# RFM23BPW_Breakout_Board.net
KiCad netlist of a schematic drawn in EAGLE
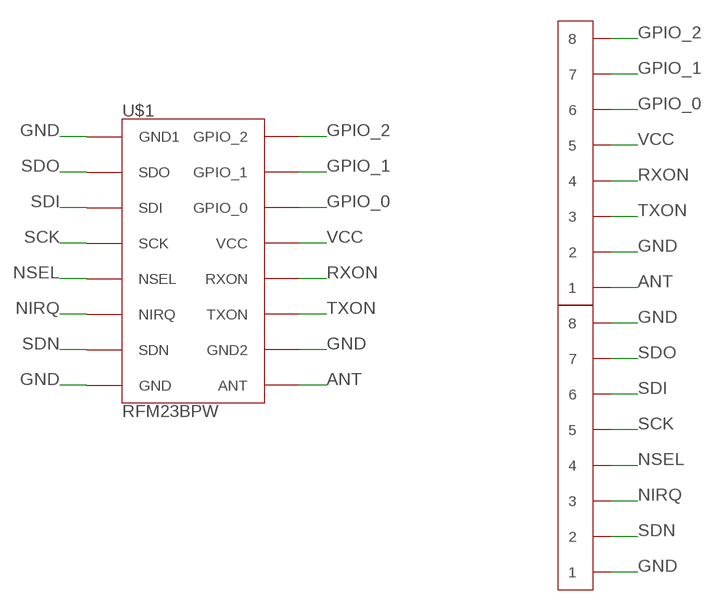
[diagram p0: schematic, sheet 1]

(export (version "E")
  (design (tool "Eeschema 10.0.6"))
  (components
    (comp (ref "U$1")
      (value "RFM23BPW")
      (footprint "eagle-import:RFM23BPW")
      (libsource (lib "eagle-import") (part "RFM23BPW"))
    )
    (comp (ref "U$2")
      (value "0.1\"_CONNECTOR_8X1")
      (footprint "eagle-import:0.1__CONNECTOR_8X1")
      (libsource (lib "eagle-import") (part "0.1{dblquote}_CONNECTOR_8X1"))
    )
    (comp (ref "U$3")
      (value "0.1\"_CONNECTOR_8X1")
      (footprint "eagle-import:0.1__CONNECTOR_8X1")
      (libsource (lib "eagle-import") (part "0.1{dblquote}_CONNECTOR_8X1"))
    )
  )
  (nets
    (net (code "1") (name "/ANT") (class "Default")
      (node (ref "U$1") (pin "16") (pinfunction "ANT_16") (pintype "bidirectional"))
      (node (ref "U$3") (pin "1") (pinfunction "1_1") (pintype "bidirectional"))
    )
    (net (code "2") (name "/GND") (class "Default")
      (node (ref "U$1") (pin "1") (pinfunction "GND_1") (pintype "bidirectional"))
      (node (ref "U$1") (pin "15") (pinfunction "GND2_15") (pintype "bidirectional"))
      (node (ref "U$1") (pin "8") (pinfunction "GND1_8") (pintype "bidirectional"))
      (node (ref "U$2") (pin "1") (pinfunction "1_1") (pintype "bidirectional"))
      (node (ref "U$2") (pin "8") (pinfunction "8_8") (pintype "bidirectional"))
      (node (ref "U$3") (pin "2") (pinfunction "2_2") (pintype "bidirectional"))
    )
    (net (code "3") (name "/GPIO_0") (class "Default")
      (node (ref "U$1") (pin "11") (pinfunction "GPIO_0_11") (pintype "bidirectional"))
      (node (ref "U$3") (pin "6") (pinfunction "6_6") (pintype "bidirectional"))
    )
    (net (code "4") (name "/GPIO_1") (class "Default")
      (node (ref "U$1") (pin "10") (pinfunction "GPIO_1_10") (pintype "bidirectional"))
      (node (ref "U$3") (pin "7") (pinfunction "7_7") (pintype "bidirectional"))
    )
    (net (code "5") (name "/GPIO_2") (class "Default")
      (node (ref "U$1") (pin "9") (pinfunction "GPIO_2_9") (pintype "bidirectional"))
      (node (ref "U$3") (pin "8") (pinfunction "8_8") (pintype "bidirectional"))
    )
    (net (code "6") (name "/NIRQ") (class "Default")
      (node (ref "U$1") (pin "3") (pinfunction "NIRQ_3") (pintype "bidirectional"))
      (node (ref "U$2") (pin "3") (pinfunction "3_3") (pintype "bidirectional"))
    )
    (net (code "7") (name "/NSEL") (class "Default")
      (node (ref "U$1") (pin "4") (pinfunction "NSEL_4") (pintype "bidirectional"))
      (node (ref "U$2") (pin "4") (pinfunction "4_4") (pintype "bidirectional"))
    )
    (net (code "8") (name "/RXON") (class "Default")
      (node (ref "U$1") (pin "13") (pinfunction "RXON_13") (pintype "bidirectional"))
      (node (ref "U$3") (pin "4") (pinfunction "4_4") (pintype "bidirectional"))
    )
    (net (code "9") (name "/SCK") (class "Default")
      (node (ref "U$1") (pin "5") (pinfunction "SCK_5") (pintype "bidirectional"))
      (node (ref "U$2") (pin "5") (pinfunction "5_5") (pintype "bidirectional"))
    )
    (net (code "10") (name "/SDI") (class "Default")
      (node (ref "U$1") (pin "6") (pinfunction "SDI_6") (pintype "bidirectional"))
      (node (ref "U$2") (pin "6") (pinfunction "6_6") (pintype "bidirectional"))
    )
    (net (code "11") (name "/SDN") (class "Default")
      (node (ref "U$1") (pin "2") (pinfunction "SDN_2") (pintype "bidirectional"))
      (node (ref "U$2") (pin "2") (pinfunction "2_2") (pintype "bidirectional"))
    )
    (net (code "12") (name "/SDO") (class "Default")
      (node (ref "U$1") (pin "7") (pinfunction "SDO_7") (pintype "bidirectional"))
      (node (ref "U$2") (pin "7") (pinfunction "7_7") (pintype "bidirectional"))
    )
    (net (code "13") (name "/TXON") (class "Default")
      (node (ref "U$1") (pin "14") (pinfunction "TXON_14") (pintype "bidirectional"))
      (node (ref "U$3") (pin "3") (pinfunction "3_3") (pintype "bidirectional"))
    )
    (net (code "14") (name "/VCC") (class "Default")
      (node (ref "U$1") (pin "12") (pinfunction "VCC_12") (pintype "bidirectional"))
      (node (ref "U$3") (pin "5") (pinfunction "5_5") (pintype "bidirectional"))
    )
  )
)
